# PowerSide.net
KiCad netlist of a schematic drawn in Altium Designer
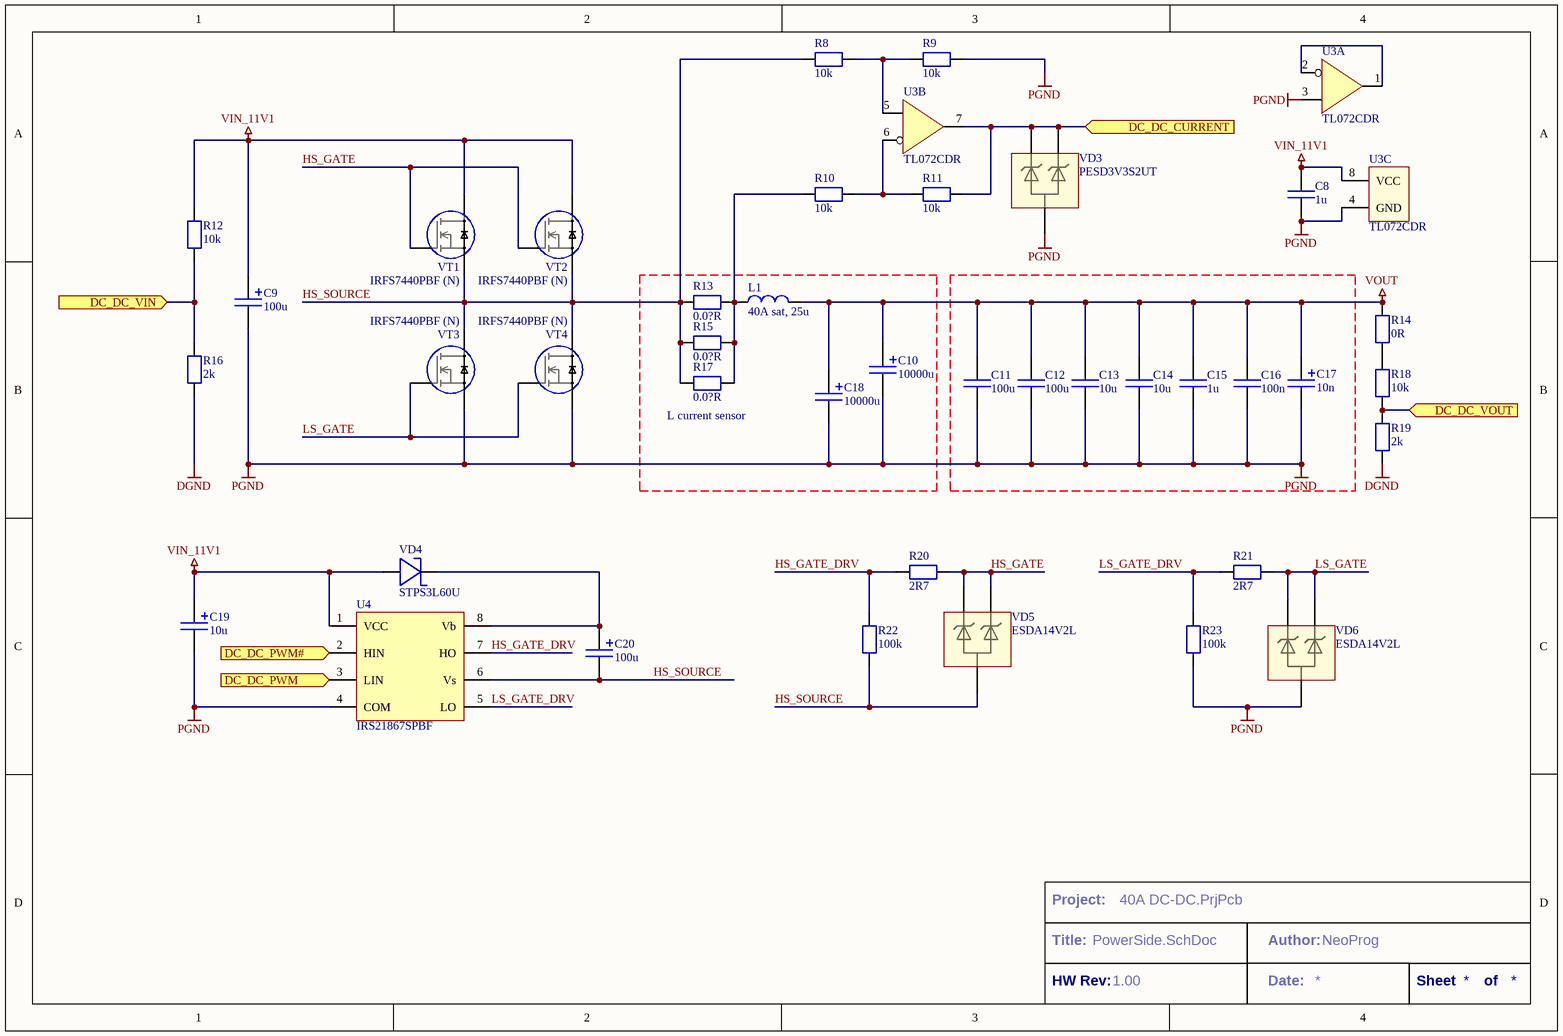
[diagram p0: PowerSide.SchDoc]

(export (version "E")
  (design (tool "Eeschema 10.0.6"))
  (components
    (comp (ref "C8")
      (value "1u")
      (footprint "C_0805/2012")
      (description "Non-polarized capacitor")
      (libsource (lib "passive") (part "Capacitor"))
    )
    (comp (ref "C9")
      (value "100u")
      (footprint "TECAP_TYPE_D")
      (description "Polarized capacitor")
      (libsource (lib "passive") (part "Capacitor polar"))
    )
    (comp (ref "C10")
      (value "10000u")
      (footprint "C_ELECTROLYTIC_6x35")
      (description "Polarized capacitor")
      (libsource (lib "passive") (part "Capacitor polar"))
    )
    (comp (ref "C11")
      (value "100u")
      (footprint "C_1206/3216")
      (description "Non-polarized capacitor")
      (libsource (lib "passive") (part "Capacitor"))
    )
    (comp (ref "C12")
      (value "100u")
      (footprint "C_1206/3216")
      (description "Non-polarized capacitor")
      (libsource (lib "passive") (part "Capacitor"))
    )
    (comp (ref "C13")
      (value "10u")
      (footprint "C_1206/3216")
      (description "Non-polarized capacitor")
      (libsource (lib "passive") (part "Capacitor"))
    )
    (comp (ref "C14")
      (value "10u")
      (footprint "C_1206/3216")
      (description "Non-polarized capacitor")
      (libsource (lib "passive") (part "Capacitor"))
    )
    (comp (ref "C15")
      (value "1u")
      (footprint "C_1206/3216")
      (description "Non-polarized capacitor")
      (libsource (lib "passive") (part "Capacitor"))
    )
    (comp (ref "C16")
      (value "100n")
      (footprint "C_1206/3216")
      (description "Non-polarized capacitor")
      (libsource (lib "passive") (part "Capacitor"))
    )
    (comp (ref "C17")
      (value "10n")
      (footprint "TECAP_TYPE_D")
      (description "Polarized capacitor")
      (libsource (lib "passive") (part "Capacitor polar"))
    )
    (comp (ref "C18")
      (value "10000u")
      (footprint "C_ELECTROLYTIC_6x35")
      (description "Polarized capacitor")
      (libsource (lib "passive") (part "Capacitor polar"))
    )
    (comp (ref "C19")
      (value "10u")
      (footprint "TECAP_TYPE_D")
      (description "Polarized capacitor")
      (libsource (lib "passive") (part "Capacitor polar"))
    )
    (comp (ref "C20")
      (value "100u")
      (footprint "TECAP_TYPE_D")
      (description "Polarized capacitor")
      (libsource (lib "passive") (part "Capacitor polar"))
    )
    (comp (ref "L1")
      (value "40A sat, 25u")
      (footprint "L_30x20x10 _SMD")
      (description "Inductor")
      (libsource (lib "passive") (part "Inductor"))
    )
    (comp (ref "R8")
      (value "10k")
      (footprint "R_0603/1608")
      (description "Resistor")
      (libsource (lib "passive") (part "Resistor"))
    )
    (comp (ref "R9")
      (value "10k")
      (footprint "R_0603/1608")
      (description "Resistor")
      (libsource (lib "passive") (part "Resistor"))
    )
    (comp (ref "R10")
      (value "10k")
      (footprint "R_0402/1005")
      (description "Resistor")
      (libsource (lib "passive") (part "Resistor"))
    )
    (comp (ref "R11")
      (value "10k")
      (footprint "R_0402/1005")
      (description "Resistor")
      (libsource (lib "passive") (part "Resistor"))
    )
    (comp (ref "R12")
      (value "10k")
      (footprint "R_0402/1005")
      (description "Resistor")
      (libsource (lib "passive") (part "Resistor"))
    )
    (comp (ref "R13")
      (value "0.0?R")
      (footprint "R_2512/6332")
      (description "Resistor")
      (libsource (lib "passive") (part "Resistor"))
    )
    (comp (ref "R14")
      (value "0R")
      (footprint "R_0603/1608")
      (description "Resistor")
      (libsource (lib "passive") (part "Resistor"))
    )
    (comp (ref "R15")
      (value "0.0?R")
      (footprint "R_2512/6332")
      (description "Resistor")
      (libsource (lib "passive") (part "Resistor"))
    )
    (comp (ref "R16")
      (value "2k")
      (footprint "R_0402/1005")
      (description "Resistor")
      (libsource (lib "passive") (part "Resistor"))
    )
    (comp (ref "R17")
      (value "0.0?R")
      (footprint "R_2512/6332")
      (description "Resistor")
      (libsource (lib "passive") (part "Resistor"))
    )
    (comp (ref "R18")
      (value "10k")
      (footprint "R_0603/1608")
      (description "Resistor")
      (libsource (lib "passive") (part "Resistor"))
    )
    (comp (ref "R19")
      (value "2k")
      (footprint "R_0603/1608")
      (description "Resistor")
      (libsource (lib "passive") (part "Resistor"))
    )
    (comp (ref "R20")
      (value "2R7")
      (footprint "R_1206/3216")
      (description "Resistor")
      (libsource (lib "passive") (part "Resistor"))
    )
    (comp (ref "R21")
      (value "2R7")
      (footprint "R_1206/3216")
      (description "Resistor")
      (libsource (lib "passive") (part "Resistor"))
    )
    (comp (ref "R22")
      (value "100k")
      (footprint "R_0805/2012")
      (description "Resistor")
      (libsource (lib "passive") (part "Resistor"))
    )
    (comp (ref "R23")
      (value "100k")
      (footprint "R_0805/2012")
      (description "Resistor")
      (libsource (lib "passive") (part "Resistor"))
    )
    (comp (ref "U3")
      (value "TL072CDR")
      (footprint "SO8_1.27")
      (description "Dual operation amplifier")
      (libsource (lib "") (part "Op-amp dual_1"))
    )
    (comp (ref "U4")
      (value "IRS21867SPBF")
      (footprint "SO8_1.27")
      (description "MOSFET driver")
      (libsource (lib "power") (part "IRS21867SPBF"))
    )
    (comp (ref "VD3")
      (value "PESD3V3S2UT")
      (footprint "SOT23-3")
      (description "TVS x2")
      (libsource (lib "active") (part "TVS x2 A-COM"))
    )
    (comp (ref "VD4")
      (value "STPS3L60U")
      (footprint "DO214AA/SMB")
      (description "Schottky diode")
      (libsource (lib "active") (part "Schottky"))
    )
    (comp (ref "VD5")
      (value "ESDA14V2L")
      (footprint "SOT23-3")
      (description "TVS x2")
      (libsource (lib "active") (part "TVS x2 A-COM"))
    )
    (comp (ref "VD6")
      (value "ESDA14V2L")
      (footprint "SOT23-3")
      (description "TVS x2")
      (libsource (lib "active") (part "TVS x2 A-COM"))
    )
    (comp (ref "VT1")
      (value "IRFS7440PBF (N)")
      (footprint "TO263-2/D2PAK-2")
      (description "MOSFET N")
      (libsource (lib "active") (part "MOSFET N"))
    )
    (comp (ref "VT2")
      (value "IRFS7440PBF (N)")
      (footprint "TO263-2/D2PAK-2")
      (description "MOSFET N")
      (libsource (lib "active") (part "MOSFET N"))
    )
    (comp (ref "VT3")
      (value "IRFS7440PBF (N)")
      (footprint "TO263-2/D2PAK-2")
      (description "MOSFET N")
      (libsource (lib "active") (part "MOSFET N"))
    )
    (comp (ref "VT4")
      (value "IRFS7440PBF (N)")
      (footprint "TO263-2/D2PAK-2")
      (description "MOSFET N")
      (libsource (lib "active") (part "MOSFET N"))
    )
  )
  (nets
    (net (code "1") (name "/DC_DC_CURRENT") (class "Default")
      (node (ref "R11") (pin "1") (pintype "passive"))
      (node (ref "U3") (pin "7") (pinfunction "OUT_7") (pintype "passive"))
      (node (ref "VD3") (pin "1C") (pinfunction "1C_1C") (pintype "passive"))
      (node (ref "VD3") (pin "2C") (pinfunction "2C_2C") (pintype "passive"))
    )
    (net (code "2") (name "/DC_DC_PWM") (class "Default")
      (node (ref "U4") (pin "3") (pinfunction "LIN_3") (pintype "passive"))
    )
    (net (code "3") (name "/DC_DC_PWM#") (class "Default")
      (node (ref "U4") (pin "2") (pinfunction "HIN_2") (pintype "passive"))
    )
    (net (code "4") (name "/DC_DC_VIN") (class "Default")
      (node (ref "R12") (pin "1") (pintype "passive"))
      (node (ref "R16") (pin "2") (pintype "passive"))
    )
    (net (code "5") (name "/DC_DC_VOUT") (class "Default")
      (node (ref "R18") (pin "1") (pintype "passive"))
      (node (ref "R19") (pin "2") (pintype "passive"))
    )
    (net (code "6") (name "/HS_GATE") (class "Default")
      (node (ref "R20") (pin "2") (pintype "passive"))
      (node (ref "VD5") (pin "1C") (pinfunction "1C_1C") (pintype "passive"))
      (node (ref "VD5") (pin "2C") (pinfunction "2C_2C") (pintype "passive"))
      (node (ref "VT1") (pin "G") (pintype "passive"))
      (node (ref "VT2") (pin "G") (pintype "passive"))
    )
    (net (code "7") (name "/HS_GATE_DRV") (class "Default")
      (node (ref "R20") (pin "1") (pintype "passive"))
      (node (ref "R22") (pin "1") (pintype "passive"))
      (node (ref "U4") (pin "7") (pinfunction "HO_7") (pintype "passive"))
    )
    (net (code "8") (name "/HS_SOURCE") (class "Default")
      (node (ref "C20") (pin "2") (pinfunction "NEG_2") (pintype "passive"))
      (node (ref "R13") (pin "2") (pintype "passive"))
      (node (ref "R15") (pin "2") (pintype "passive"))
      (node (ref "R17") (pin "2") (pintype "passive"))
      (node (ref "R22") (pin "2") (pintype "passive"))
      (node (ref "R8") (pin "2") (pintype "passive"))
      (node (ref "U4") (pin "6") (pinfunction "Vs_6") (pintype "passive"))
      (node (ref "VD5") (pin "A") (pinfunction "A_A") (pintype "passive"))
      (node (ref "VT1") (pin "S") (pintype "passive"))
      (node (ref "VT2") (pin "S") (pintype "passive"))
      (node (ref "VT3") (pin "D") (pintype "passive"))
      (node (ref "VT4") (pin "D") (pintype "passive"))
    )
    (net (code "9") (name "/LS_GATE") (class "Default")
      (node (ref "R21") (pin "2") (pintype "passive"))
      (node (ref "VD6") (pin "1C") (pinfunction "1C_1C") (pintype "passive"))
      (node (ref "VD6") (pin "2C") (pinfunction "2C_2C") (pintype "passive"))
      (node (ref "VT3") (pin "G") (pintype "passive"))
      (node (ref "VT4") (pin "G") (pintype "passive"))
    )
    (net (code "10") (name "/LS_GATE_DRV") (class "Default")
      (node (ref "R21") (pin "1") (pintype "passive"))
      (node (ref "R23") (pin "1") (pintype "passive"))
      (node (ref "U4") (pin "5") (pinfunction "LO_5") (pintype "passive"))
    )
    (net (code "11") (name "DGND") (class "Default")
      (node (ref "R16") (pin "1") (pintype "passive"))
      (node (ref "R19") (pin "1") (pintype "passive"))
    )
    (net (code "12") (name "Net-(C20-POS)") (class "Default")
      (node (ref "C20") (pin "1") (pinfunction "POS_1") (pintype "passive"))
      (node (ref "U4") (pin "8") (pinfunction "Vb_8") (pintype "passive"))
      (node (ref "VD4") (pin "C") (pinfunction "C`_C") (pintype "passive"))
    )
    (net (code "13") (name "Net-(L1-Pad1)") (class "Default")
      (node (ref "L1") (pin "1") (pintype "passive"))
      (node (ref "R10") (pin "2") (pintype "passive"))
      (node (ref "R13") (pin "1") (pintype "passive"))
      (node (ref "R15") (pin "1") (pintype "passive"))
      (node (ref "R17") (pin "1") (pintype "passive"))
    )
    (net (code "14") (name "Net-(R8-Pad1)") (class "Default")
      (node (ref "R8") (pin "1") (pintype "passive"))
      (node (ref "R9") (pin "2") (pintype "passive"))
      (node (ref "U3") (pin "5") (pintype "passive"))
    )
    (net (code "15") (name "Net-(R10-Pad1)") (class "Default")
      (node (ref "R10") (pin "1") (pintype "passive"))
      (node (ref "R11") (pin "2") (pintype "passive"))
      (node (ref "U3") (pin "6") (pintype "passive"))
    )
    (net (code "16") (name "Net-(R14-Pad1)") (class "Default")
      (node (ref "R14") (pin "1") (pintype "passive"))
      (node (ref "R18") (pin "2") (pintype "passive"))
    )
    (net (code "17") (name "Net-(U3A-OUT)") (class "Default")
      (node (ref "U3") (pin "1") (pinfunction "OUT_1") (pintype "passive"))
      (node (ref "U3") (pin "2") (pintype "passive"))
    )
    (net (code "18") (name "PGND") (class "Default")
      (node (ref "C10") (pin "2") (pinfunction "NEG_2") (pintype "passive"))
      (node (ref "C11") (pin "1") (pintype "passive"))
      (node (ref "C12") (pin "1") (pintype "passive"))
      (node (ref "C13") (pin "1") (pintype "passive"))
      (node (ref "C14") (pin "1") (pintype "passive"))
      (node (ref "C15") (pin "1") (pintype "passive"))
      (node (ref "C16") (pin "1") (pintype "passive"))
      (node (ref "C17") (pin "2") (pinfunction "NEG_2") (pintype "passive"))
      (node (ref "C18") (pin "2") (pinfunction "NEG_2") (pintype "passive"))
      (node (ref "C19") (pin "2") (pinfunction "NEG_2") (pintype "passive"))
      (node (ref "C8") (pin "1") (pintype "passive"))
      (node (ref "C9") (pin "2") (pinfunction "NEG_2") (pintype "passive"))
      (node (ref "R23") (pin "2") (pintype "passive"))
      (node (ref "R9") (pin "1") (pintype "passive"))
      (node (ref "U3") (pin "3") (pintype "passive"))
      (node (ref "U3") (pin "4") (pinfunction "GND_4") (pintype "power_in"))
      (node (ref "U4") (pin "4") (pinfunction "COM_4") (pintype "passive"))
      (node (ref "VD3") (pin "A") (pinfunction "A_A") (pintype "passive"))
      (node (ref "VD6") (pin "A") (pinfunction "A_A") (pintype "passive"))
      (node (ref "VT3") (pin "S") (pintype "passive"))
      (node (ref "VT4") (pin "S") (pintype "passive"))
    )
    (net (code "19") (name "VIN_11V1") (class "Default")
      (node (ref "C19") (pin "1") (pinfunction "POS_1") (pintype "passive"))
      (node (ref "C8") (pin "2") (pintype "passive"))
      (node (ref "C9") (pin "1") (pinfunction "POS_1") (pintype "passive"))
      (node (ref "R12") (pin "2") (pintype "passive"))
      (node (ref "U3") (pin "8") (pinfunction "VCC_8") (pintype "power_in"))
      (node (ref "U4") (pin "1") (pinfunction "VCC_1") (pintype "passive"))
      (node (ref "VD4") (pin "A") (pinfunction "A_A") (pintype "passive"))
      (node (ref "VT1") (pin "D") (pintype "passive"))
      (node (ref "VT2") (pin "D") (pintype "passive"))
    )
    (net (code "20") (name "VOUT") (class "Default")
      (node (ref "C10") (pin "1") (pinfunction "POS_1") (pintype "passive"))
      (node (ref "C11") (pin "2") (pintype "passive"))
      (node (ref "C12") (pin "2") (pintype "passive"))
      (node (ref "C13") (pin "2") (pintype "passive"))
      (node (ref "C14") (pin "2") (pintype "passive"))
      (node (ref "C15") (pin "2") (pintype "passive"))
      (node (ref "C16") (pin "2") (pintype "passive"))
      (node (ref "C17") (pin "1") (pinfunction "POS_1") (pintype "passive"))
      (node (ref "C18") (pin "1") (pinfunction "POS_1") (pintype "passive"))
      (node (ref "L1") (pin "2") (pintype "passive"))
      (node (ref "R14") (pin "2") (pintype "passive"))
    )
  )
)
